# Inter.net
KiCad netlist of a schematic drawn in EAGLE
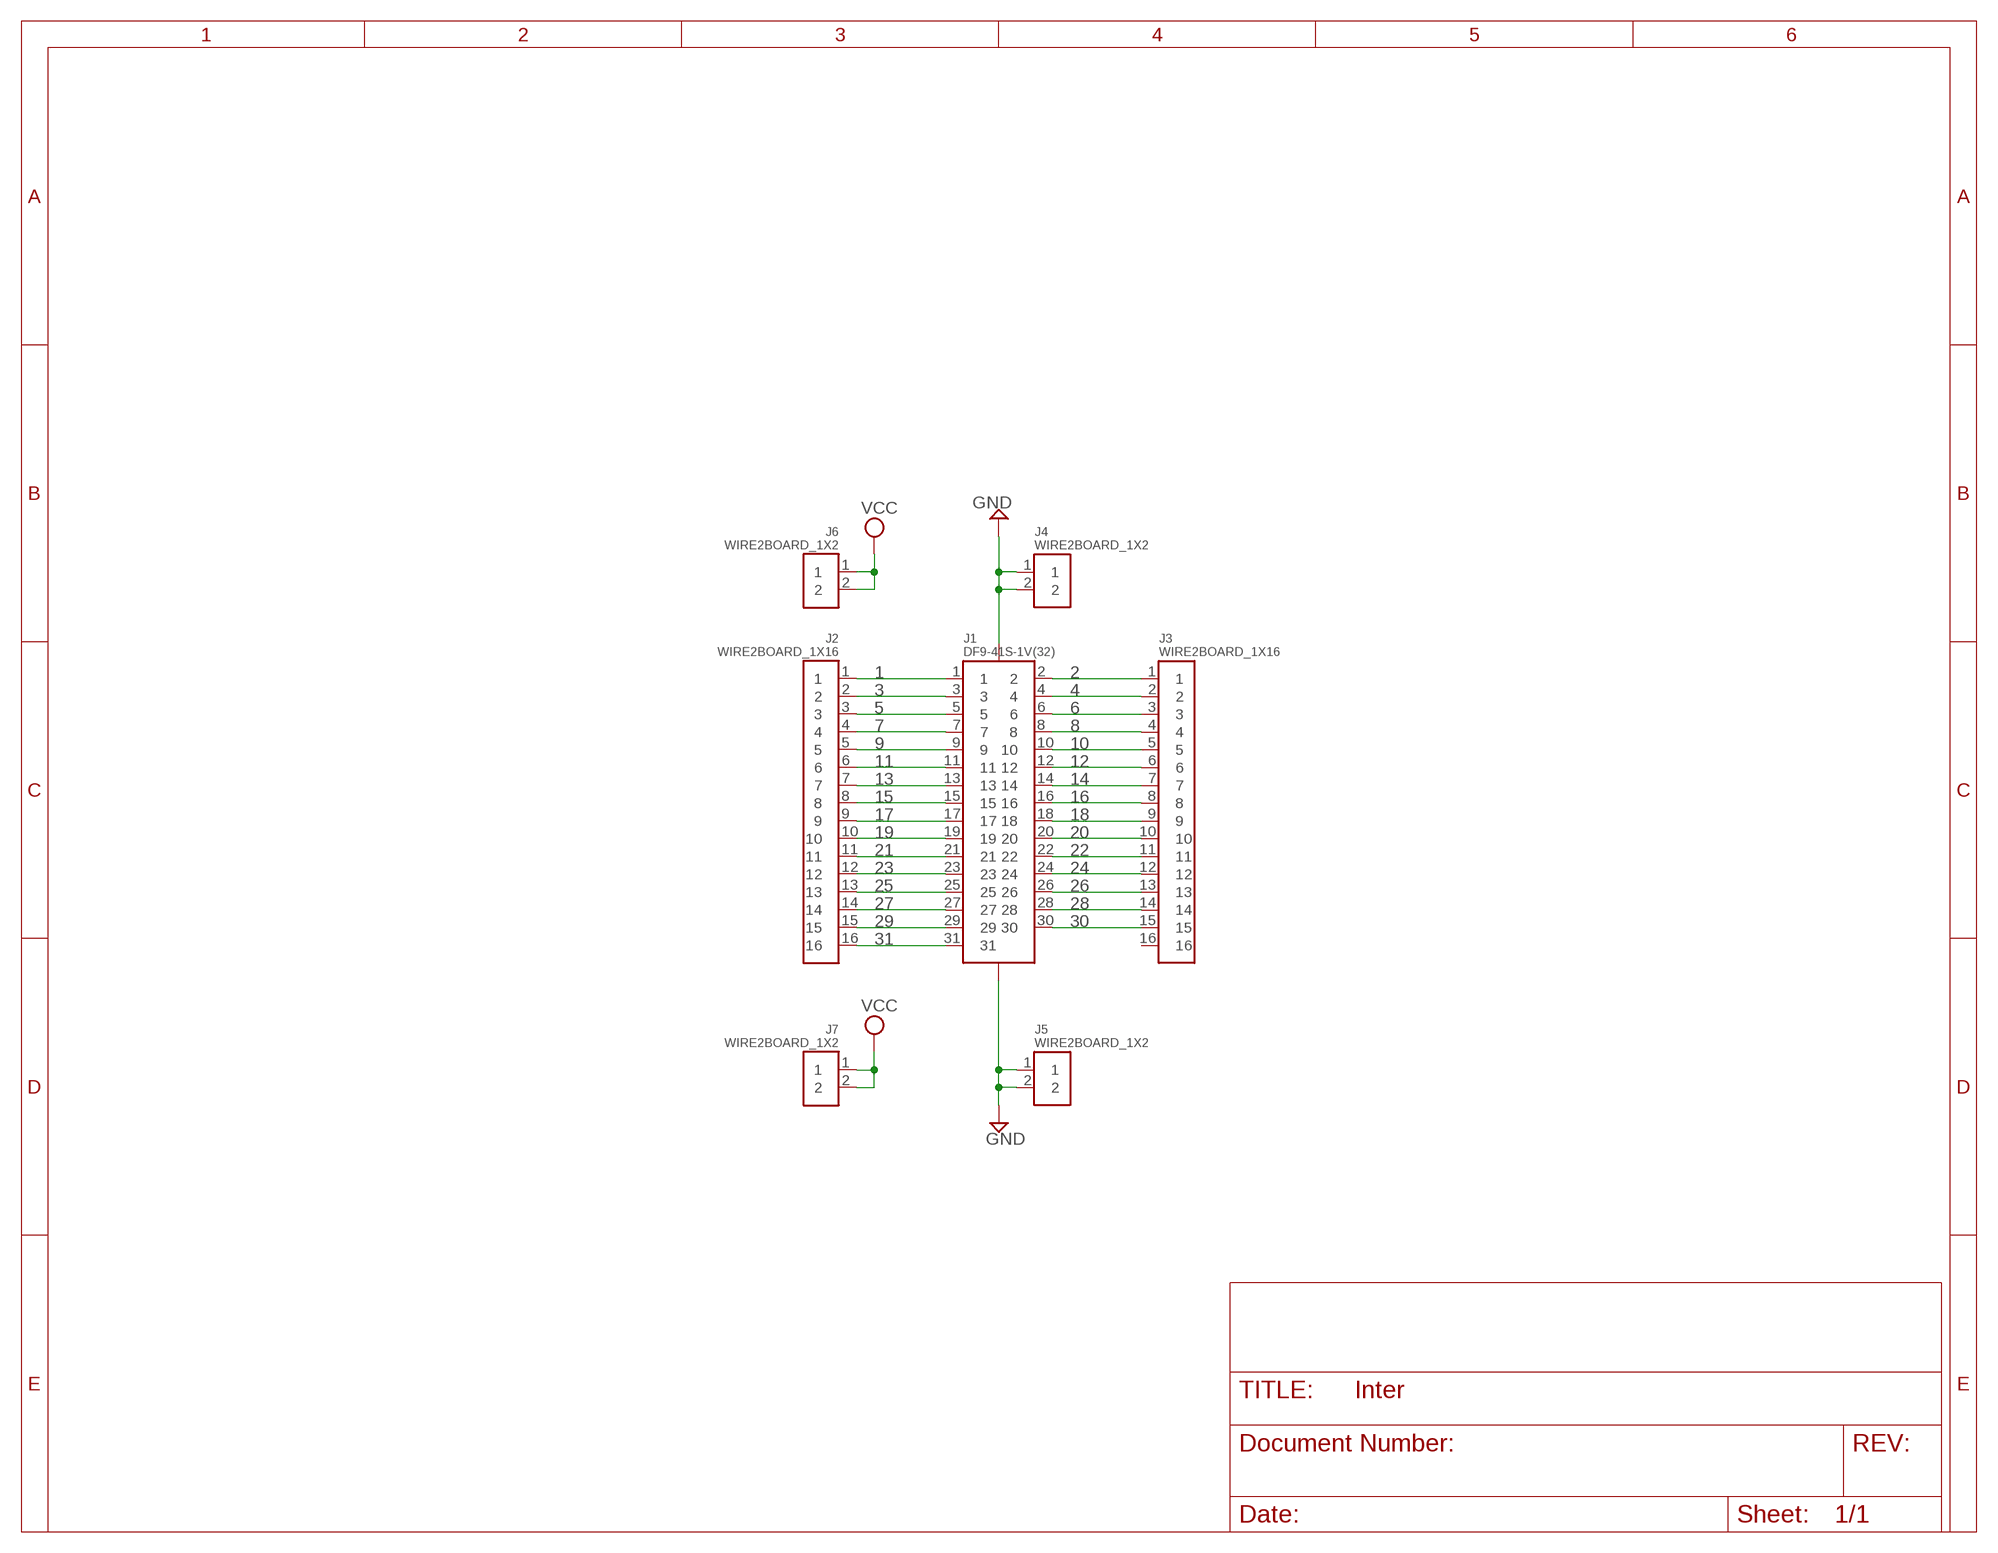
[diagram p0: schematic, sheet 1]

(export (version "E")
  (design (tool "Eeschema 10.0.6"))
  (components
    (comp (ref "J1")
      (value "DF9-41S-1V(32)")
      (footprint "eagle-import:DF9-41S-1V(32)")
      (libsource (lib "eagle-import") (part "DF9-41S-1V(32)"))
    )
    (comp (ref "J2")
      (value "WIRE2BOARD_1X16")
      (footprint "eagle-import:WIRE2BOARD_1X16")
      (libsource (lib "eagle-import") (part "WIRE2BOARD_1X16"))
    )
    (comp (ref "J3")
      (value "WIRE2BOARD_1X16")
      (footprint "eagle-import:WIRE2BOARD_1X16")
      (libsource (lib "eagle-import") (part "WIRE2BOARD_1X16"))
    )
    (comp (ref "J4")
      (value "WIRE2BOARD_1X2")
      (footprint "eagle-import:WIRE2BOARD_1X2")
      (libsource (lib "eagle-import") (part "WIRE2BOARD_1X2"))
    )
    (comp (ref "J5")
      (value "WIRE2BOARD_1X2")
      (footprint "eagle-import:WIRE2BOARD_1X2")
      (libsource (lib "eagle-import") (part "WIRE2BOARD_1X2"))
    )
    (comp (ref "J6")
      (value "WIRE2BOARD_1X2")
      (footprint "eagle-import:WIRE2BOARD_1X2")
      (libsource (lib "eagle-import") (part "WIRE2BOARD_1X2"))
    )
    (comp (ref "J7")
      (value "WIRE2BOARD_1X2")
      (footprint "eagle-import:WIRE2BOARD_1X2")
      (libsource (lib "eagle-import") (part "WIRE2BOARD_1X2"))
    )
  )
  (nets
    (net (code "1") (name "/1") (class "Default")
      (node (ref "J1") (pin "1") (pinfunction "1_1") (pintype "bidirectional"))
      (node (ref "J2") (pin "1") (pinfunction "1_1") (pintype "bidirectional"))
    )
    (net (code "2") (name "/2") (class "Default")
      (node (ref "J1") (pin "2") (pinfunction "2_2") (pintype "bidirectional"))
      (node (ref "J3") (pin "1") (pinfunction "1_1") (pintype "bidirectional"))
    )
    (net (code "3") (name "/3") (class "Default")
      (node (ref "J1") (pin "3") (pinfunction "3_3") (pintype "bidirectional"))
      (node (ref "J2") (pin "2") (pinfunction "2_2") (pintype "bidirectional"))
    )
    (net (code "4") (name "/4") (class "Default")
      (node (ref "J1") (pin "4") (pinfunction "4_4") (pintype "bidirectional"))
      (node (ref "J3") (pin "2") (pinfunction "2_2") (pintype "bidirectional"))
    )
    (net (code "5") (name "/5") (class "Default")
      (node (ref "J1") (pin "5") (pinfunction "5_5") (pintype "bidirectional"))
      (node (ref "J2") (pin "3") (pinfunction "3_3") (pintype "bidirectional"))
    )
    (net (code "6") (name "/6") (class "Default")
      (node (ref "J1") (pin "6") (pinfunction "6_6") (pintype "bidirectional"))
      (node (ref "J3") (pin "3") (pinfunction "3_3") (pintype "bidirectional"))
    )
    (net (code "7") (name "/7") (class "Default")
      (node (ref "J1") (pin "7") (pinfunction "7_7") (pintype "bidirectional"))
      (node (ref "J2") (pin "4") (pinfunction "4_4") (pintype "bidirectional"))
    )
    (net (code "8") (name "/8") (class "Default")
      (node (ref "J1") (pin "8") (pinfunction "8_8") (pintype "bidirectional"))
      (node (ref "J3") (pin "4") (pinfunction "4_4") (pintype "bidirectional"))
    )
    (net (code "9") (name "/9") (class "Default")
      (node (ref "J1") (pin "9") (pinfunction "9_9") (pintype "bidirectional"))
      (node (ref "J2") (pin "5") (pinfunction "5_5") (pintype "bidirectional"))
    )
    (net (code "10") (name "/10") (class "Default")
      (node (ref "J1") (pin "10") (pinfunction "10_10") (pintype "bidirectional"))
      (node (ref "J3") (pin "5") (pinfunction "5_5") (pintype "bidirectional"))
    )
    (net (code "11") (name "/11") (class "Default")
      (node (ref "J1") (pin "11") (pinfunction "11_11") (pintype "bidirectional"))
      (node (ref "J2") (pin "6") (pinfunction "6_6") (pintype "bidirectional"))
    )
    (net (code "12") (name "/12") (class "Default")
      (node (ref "J1") (pin "12") (pinfunction "12_12") (pintype "bidirectional"))
      (node (ref "J3") (pin "6") (pinfunction "6_6") (pintype "bidirectional"))
    )
    (net (code "13") (name "/13") (class "Default")
      (node (ref "J1") (pin "13") (pinfunction "13_13") (pintype "bidirectional"))
      (node (ref "J2") (pin "7") (pinfunction "7_7") (pintype "bidirectional"))
    )
    (net (code "14") (name "/14") (class "Default")
      (node (ref "J1") (pin "14") (pinfunction "14_14") (pintype "bidirectional"))
      (node (ref "J3") (pin "7") (pinfunction "7_7") (pintype "bidirectional"))
    )
    (net (code "15") (name "/15") (class "Default")
      (node (ref "J1") (pin "15") (pinfunction "15_15") (pintype "bidirectional"))
      (node (ref "J2") (pin "8") (pinfunction "8_8") (pintype "bidirectional"))
    )
    (net (code "16") (name "/16") (class "Default")
      (node (ref "J1") (pin "16") (pinfunction "16_16") (pintype "bidirectional"))
      (node (ref "J3") (pin "8") (pinfunction "8_8") (pintype "bidirectional"))
    )
    (net (code "17") (name "/17") (class "Default")
      (node (ref "J1") (pin "17") (pinfunction "17_17") (pintype "bidirectional"))
      (node (ref "J2") (pin "9") (pinfunction "9_9") (pintype "bidirectional"))
    )
    (net (code "18") (name "/18") (class "Default")
      (node (ref "J1") (pin "18") (pinfunction "18_18") (pintype "bidirectional"))
      (node (ref "J3") (pin "9") (pinfunction "9_9") (pintype "bidirectional"))
    )
    (net (code "19") (name "/19") (class "Default")
      (node (ref "J1") (pin "19") (pinfunction "19_19") (pintype "bidirectional"))
      (node (ref "J2") (pin "10") (pinfunction "10_10") (pintype "bidirectional"))
    )
    (net (code "20") (name "/20") (class "Default")
      (node (ref "J1") (pin "20") (pinfunction "20_20") (pintype "bidirectional"))
      (node (ref "J3") (pin "10") (pinfunction "10_10") (pintype "bidirectional"))
    )
    (net (code "21") (name "/21") (class "Default")
      (node (ref "J1") (pin "21") (pinfunction "21_21") (pintype "bidirectional"))
      (node (ref "J2") (pin "11") (pinfunction "11_11") (pintype "bidirectional"))
    )
    (net (code "22") (name "/22") (class "Default")
      (node (ref "J1") (pin "22") (pinfunction "22_22") (pintype "bidirectional"))
      (node (ref "J3") (pin "11") (pinfunction "11_11") (pintype "bidirectional"))
    )
    (net (code "23") (name "/23") (class "Default")
      (node (ref "J1") (pin "23") (pinfunction "23_23") (pintype "bidirectional"))
      (node (ref "J2") (pin "12") (pinfunction "12_12") (pintype "bidirectional"))
    )
    (net (code "24") (name "/24") (class "Default")
      (node (ref "J1") (pin "24") (pinfunction "24_24") (pintype "bidirectional"))
      (node (ref "J3") (pin "12") (pinfunction "12_12") (pintype "bidirectional"))
    )
    (net (code "25") (name "/25") (class "Default")
      (node (ref "J1") (pin "25") (pinfunction "25_25") (pintype "bidirectional"))
      (node (ref "J2") (pin "13") (pinfunction "13_13") (pintype "bidirectional"))
    )
    (net (code "26") (name "/26") (class "Default")
      (node (ref "J1") (pin "26") (pinfunction "26_26") (pintype "bidirectional"))
      (node (ref "J3") (pin "13") (pinfunction "13_13") (pintype "bidirectional"))
    )
    (net (code "27") (name "/27") (class "Default")
      (node (ref "J1") (pin "27") (pinfunction "27_27") (pintype "bidirectional"))
      (node (ref "J2") (pin "14") (pinfunction "14_14") (pintype "bidirectional"))
    )
    (net (code "28") (name "/28") (class "Default")
      (node (ref "J1") (pin "28") (pinfunction "28_28") (pintype "bidirectional"))
      (node (ref "J3") (pin "14") (pinfunction "14_14") (pintype "bidirectional"))
    )
    (net (code "29") (name "/29") (class "Default")
      (node (ref "J1") (pin "29") (pinfunction "29_29") (pintype "bidirectional"))
      (node (ref "J2") (pin "15") (pinfunction "15_15") (pintype "bidirectional"))
    )
    (net (code "30") (name "/30") (class "Default")
      (node (ref "J1") (pin "30") (pinfunction "30_30") (pintype "bidirectional"))
      (node (ref "J3") (pin "15") (pinfunction "15_15") (pintype "bidirectional"))
    )
    (net (code "31") (name "/31") (class "Default")
      (node (ref "J1") (pin "31") (pinfunction "31_31") (pintype "bidirectional"))
      (node (ref "J2") (pin "16") (pinfunction "16_16") (pintype "bidirectional"))
    )
    (net (code "32") (name "GND") (class "Default")
      (node (ref "J1") (pin "32") (pinfunction "32_32") (pintype "bidirectional"))
      (node (ref "J1") (pin "33") (pinfunction "33_33") (pintype "bidirectional"))
      (node (ref "J4") (pin "1") (pinfunction "1_1") (pintype "bidirectional"))
      (node (ref "J4") (pin "2") (pinfunction "2_2") (pintype "bidirectional"))
      (node (ref "J5") (pin "1") (pinfunction "1_1") (pintype "bidirectional"))
      (node (ref "J5") (pin "2") (pinfunction "2_2") (pintype "bidirectional"))
    )
    (net (code "33") (name "VCC") (class "Default")
      (node (ref "J6") (pin "1") (pinfunction "1_1") (pintype "bidirectional"))
      (node (ref "J6") (pin "2") (pinfunction "2_2") (pintype "bidirectional"))
      (node (ref "J7") (pin "1") (pinfunction "1_1") (pintype "bidirectional"))
      (node (ref "J7") (pin "2") (pinfunction "2_2") (pintype "bidirectional"))
    )
    (net (code "34") (name "unconnected-(J3-Pad16)") (class "Default")
      (node (ref "J3") (pin "16") (pinfunction "16_16") (pintype "bidirectional"))
    )
  )
)
